# ProPrj_chuni_24_2026-08-18.net
KiCad netlist of a schematic drawn in EasyEDA Pro
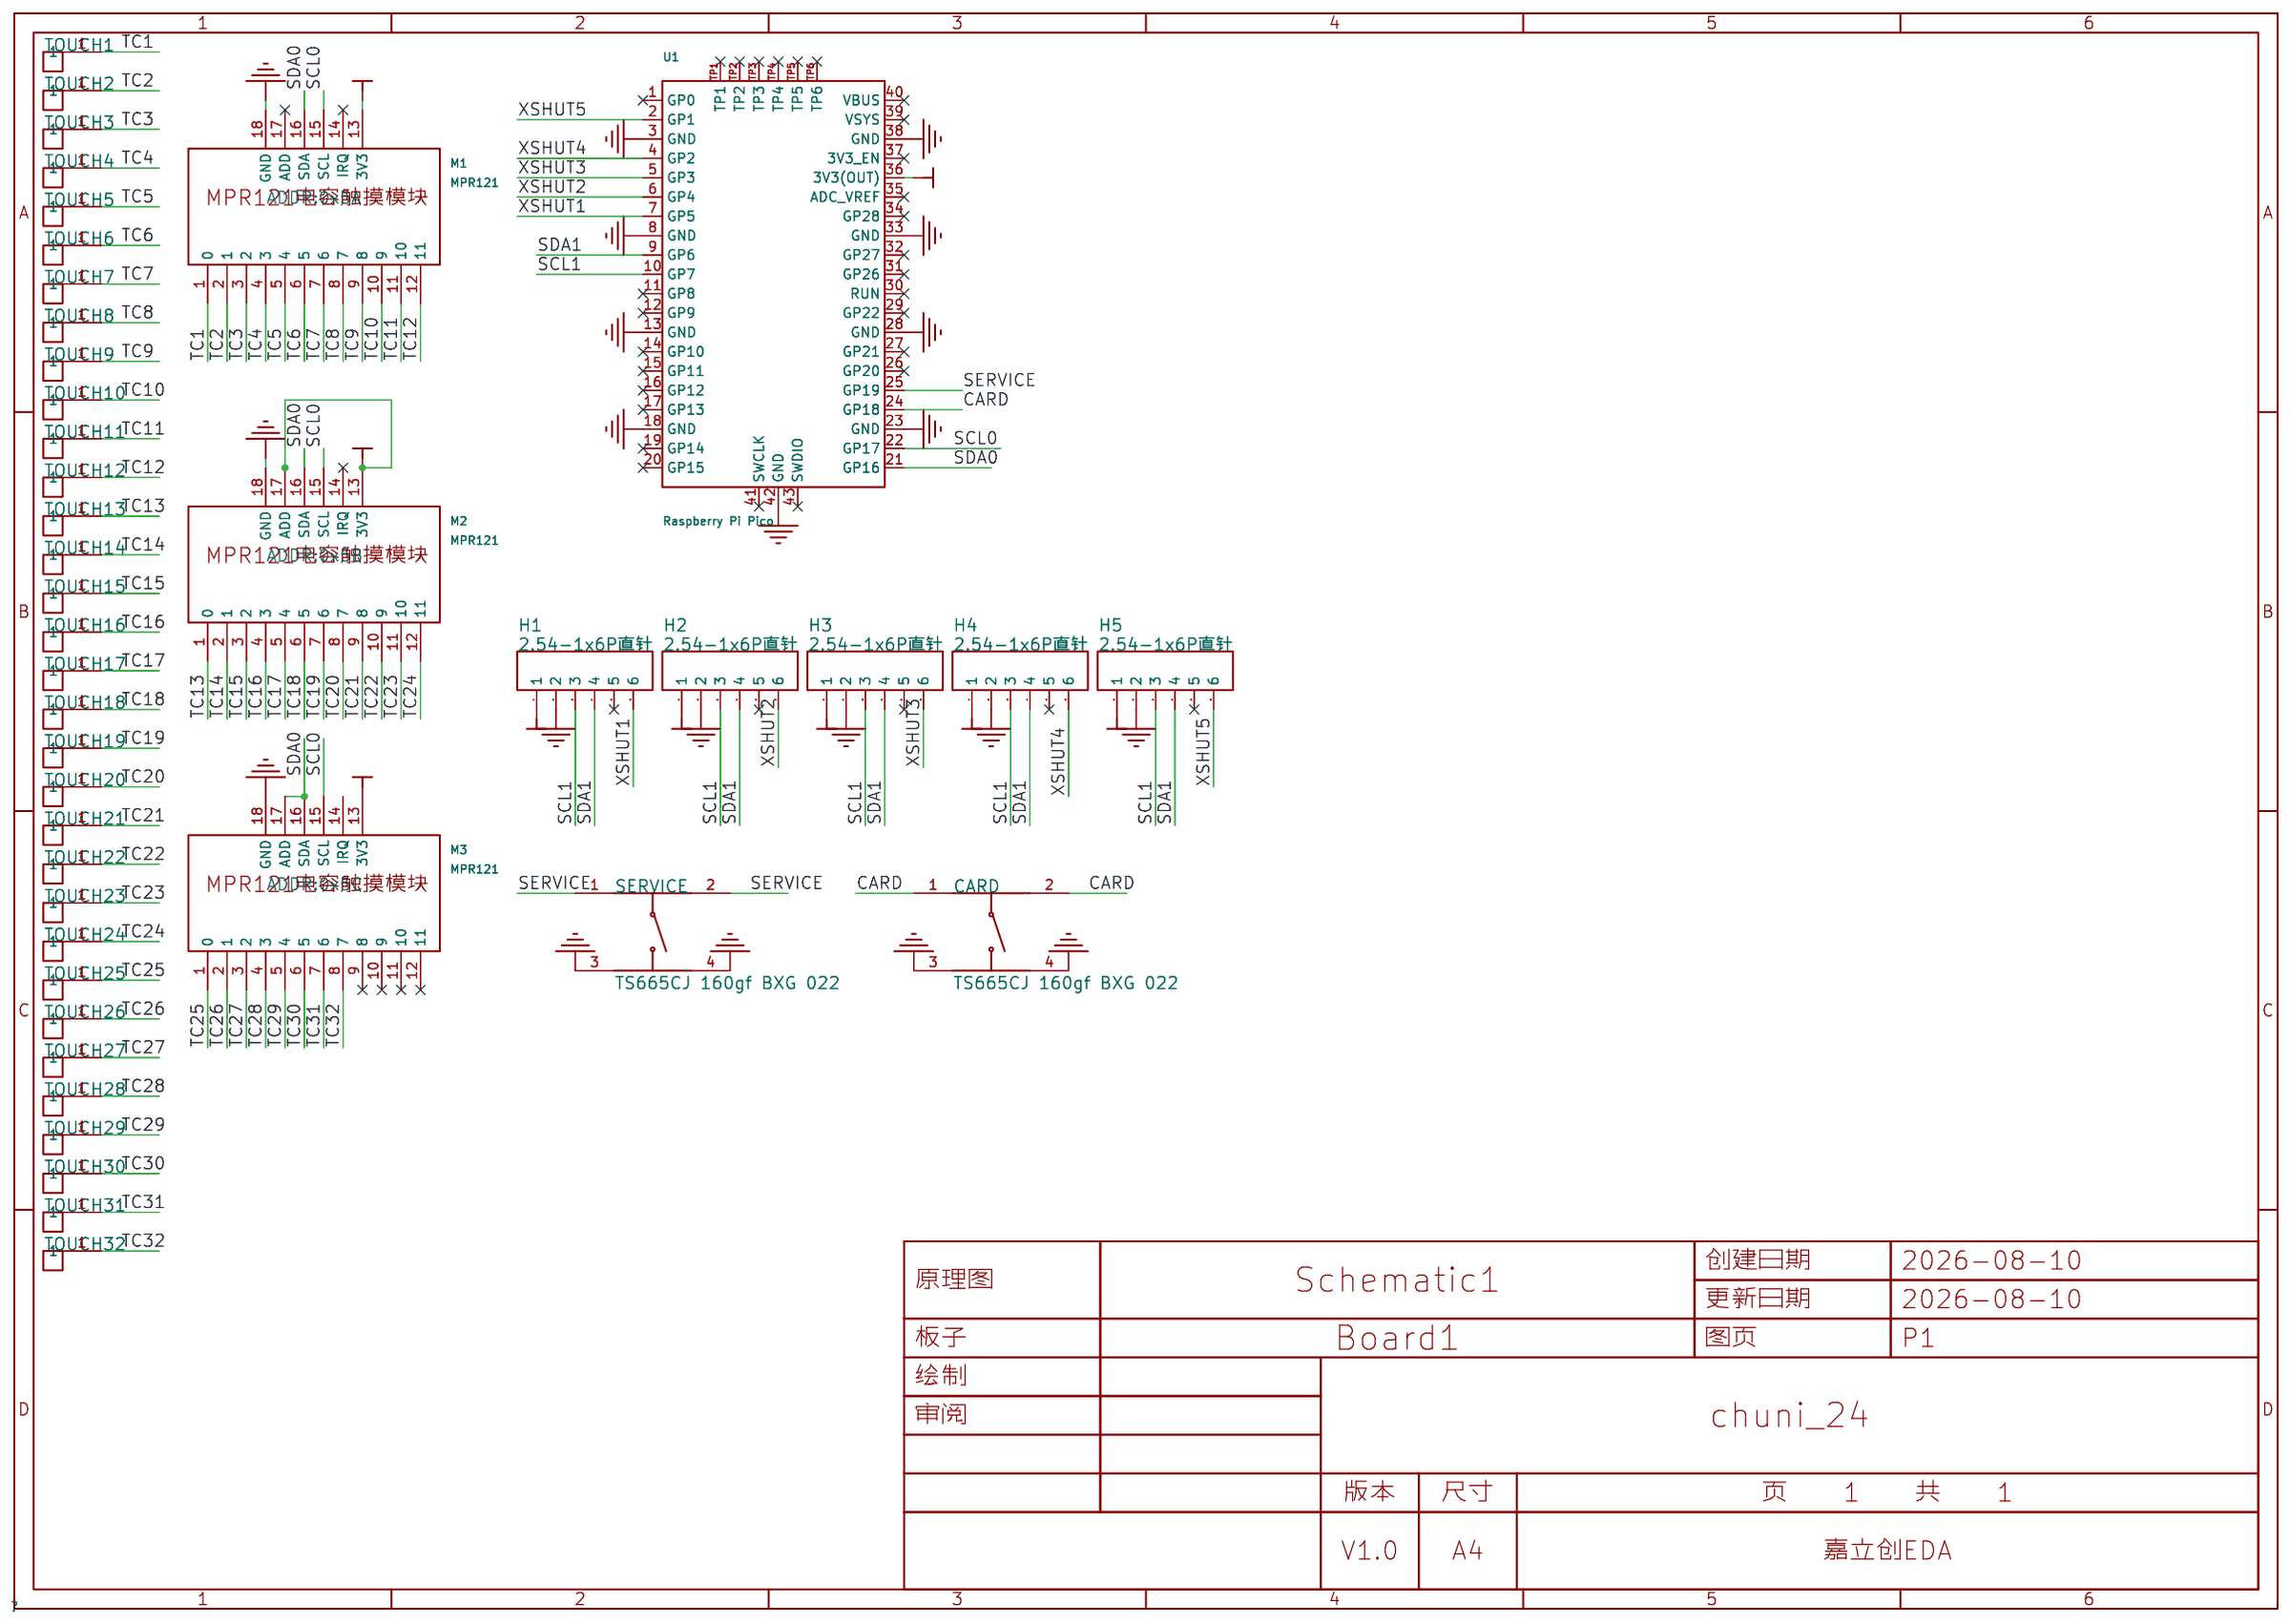
[diagram p0: schematic sheet]

(export (version "E")
  (design (tool "Eeschema 10.0.6"))
  (components
    (comp (ref "CARD")
      (value "TS665CJ 160gf BXG 022")
      (footprint "easyedapro:SW-TH_4P-L6.0-W6.0-P4.50-LS6.5")
      (fields (field (name "Manufacturer") "SHOU HAN(首韩)"))
      (libsource (lib "easyedapro") (part "TS665CJ 160GF BXG 022"))
    )
    (comp (ref "H1")
      (value "2.54-1x6P直针")
      (footprint "easyedapro:HDR-TH_6P-P2.54-V-M-1")
      (fields (field (name "Manufacturer") "BOOMELE(博穆精密)"))
      (libsource (lib "easyedapro") (part "Header-Male-2.54_1x6"))
    )
    (comp (ref "H2")
      (value "2.54-1x6P直针")
      (footprint "easyedapro:HDR-TH_6P-P2.54-V-M-1")
      (fields (field (name "Manufacturer") "BOOMELE(博穆精密)"))
      (libsource (lib "easyedapro") (part "Header-Male-2.54_1x6"))
    )
    (comp (ref "H3")
      (value "2.54-1x6P直针")
      (footprint "easyedapro:HDR-TH_6P-P2.54-V-M-1")
      (fields (field (name "Manufacturer") "BOOMELE(博穆精密)"))
      (libsource (lib "easyedapro") (part "Header-Male-2.54_1x6"))
    )
    (comp (ref "H4")
      (value "2.54-1x6P直针")
      (footprint "easyedapro:HDR-TH_6P-P2.54-V-M-1")
      (fields (field (name "Manufacturer") "BOOMELE(博穆精密)"))
      (libsource (lib "easyedapro") (part "Header-Male-2.54_1x6"))
    )
    (comp (ref "H5")
      (value "2.54-1x6P直针")
      (footprint "easyedapro:HDR-TH_6P-P2.54-V-M-1")
      (fields (field (name "Manufacturer") "BOOMELE(博穆精密)"))
      (libsource (lib "easyedapro") (part "Header-Male-2.54_1x6"))
    )
    (comp (ref "M1")
      (value "MPR121")
      (footprint "easyedapro:MPR121")
      (libsource (lib "easyedapro") (part "MPR121"))
    )
    (comp (ref "M2")
      (value "MPR121")
      (footprint "easyedapro:MPR121")
      (libsource (lib "easyedapro") (part "MPR121"))
    )
    (comp (ref "M3")
      (value "MPR121")
      (footprint "easyedapro:MPR121")
      (libsource (lib "easyedapro") (part "MPR121"))
    )
    (comp (ref "SERVICE")
      (value "TS665CJ 160gf BXG 022")
      (footprint "easyedapro:SW-TH_4P-L6.0-W6.0-P4.50-LS6.5")
      (fields (field (name "Manufacturer") "SHOU HAN(首韩)"))
      (libsource (lib "easyedapro") (part "TS665CJ 160GF BXG 022"))
    )
    (comp (ref "TOUCH1")
      (value "~")
      (footprint "easyedapro:touch_24.5")
      (libsource (lib "easyedapro") (part "touch_24.5"))
    )
    (comp (ref "TOUCH2")
      (value "~")
      (footprint "easyedapro:touch_24.5")
      (libsource (lib "easyedapro") (part "touch_24.5"))
    )
    (comp (ref "TOUCH3")
      (value "~")
      (footprint "easyedapro:touch_24.5")
      (libsource (lib "easyedapro") (part "touch_24.5"))
    )
    (comp (ref "TOUCH4")
      (value "~")
      (footprint "easyedapro:touch_24.5")
      (libsource (lib "easyedapro") (part "touch_24.5"))
    )
    (comp (ref "TOUCH5")
      (value "~")
      (footprint "easyedapro:touch_24.5")
      (libsource (lib "easyedapro") (part "touch_24.5"))
    )
    (comp (ref "TOUCH6")
      (value "~")
      (footprint "easyedapro:touch_24.5")
      (libsource (lib "easyedapro") (part "touch_24.5"))
    )
    (comp (ref "TOUCH7")
      (value "~")
      (footprint "easyedapro:touch_24.5")
      (libsource (lib "easyedapro") (part "touch_24.5"))
    )
    (comp (ref "TOUCH8")
      (value "~")
      (footprint "easyedapro:touch_24.5")
      (libsource (lib "easyedapro") (part "touch_24.5"))
    )
    (comp (ref "TOUCH9")
      (value "~")
      (footprint "easyedapro:touch_24.5")
      (libsource (lib "easyedapro") (part "touch_24.5"))
    )
    (comp (ref "TOUCH10")
      (value "~")
      (footprint "easyedapro:touch_24.5")
      (libsource (lib "easyedapro") (part "touch_24.5"))
    )
    (comp (ref "TOUCH11")
      (value "~")
      (footprint "easyedapro:touch_24.5")
      (libsource (lib "easyedapro") (part "touch_24.5"))
    )
    (comp (ref "TOUCH12")
      (value "~")
      (footprint "easyedapro:touch_24.5")
      (libsource (lib "easyedapro") (part "touch_24.5"))
    )
    (comp (ref "TOUCH13")
      (value "~")
      (footprint "easyedapro:touch_24.5")
      (libsource (lib "easyedapro") (part "touch_24.5"))
    )
    (comp (ref "TOUCH14")
      (value "~")
      (footprint "easyedapro:touch_24.5")
      (libsource (lib "easyedapro") (part "touch_24.5"))
    )
    (comp (ref "TOUCH15")
      (value "~")
      (footprint "easyedapro:touch_24.5")
      (libsource (lib "easyedapro") (part "touch_24.5"))
    )
    (comp (ref "TOUCH16")
      (value "~")
      (footprint "easyedapro:touch_24.5")
      (libsource (lib "easyedapro") (part "touch_24.5"))
    )
    (comp (ref "TOUCH17")
      (value "~")
      (footprint "easyedapro:touch_24.5")
      (libsource (lib "easyedapro") (part "touch_24.5"))
    )
    (comp (ref "TOUCH18")
      (value "~")
      (footprint "easyedapro:touch_24.5")
      (libsource (lib "easyedapro") (part "touch_24.5"))
    )
    (comp (ref "TOUCH19")
      (value "~")
      (footprint "easyedapro:touch_24.5")
      (libsource (lib "easyedapro") (part "touch_24.5"))
    )
    (comp (ref "TOUCH20")
      (value "~")
      (footprint "easyedapro:touch_24.5")
      (libsource (lib "easyedapro") (part "touch_24.5"))
    )
    (comp (ref "TOUCH21")
      (value "~")
      (footprint "easyedapro:touch_24.5")
      (libsource (lib "easyedapro") (part "touch_24.5"))
    )
    (comp (ref "TOUCH22")
      (value "~")
      (footprint "easyedapro:touch_24.5")
      (libsource (lib "easyedapro") (part "touch_24.5"))
    )
    (comp (ref "TOUCH23")
      (value "~")
      (footprint "easyedapro:touch_24.5")
      (libsource (lib "easyedapro") (part "touch_24.5"))
    )
    (comp (ref "TOUCH24")
      (value "~")
      (footprint "easyedapro:touch_24.5")
      (libsource (lib "easyedapro") (part "touch_24.5"))
    )
    (comp (ref "TOUCH25")
      (value "~")
      (footprint "easyedapro:touch_24.5")
      (libsource (lib "easyedapro") (part "touch_24.5"))
    )
    (comp (ref "TOUCH26")
      (value "~")
      (footprint "easyedapro:touch_24.5")
      (libsource (lib "easyedapro") (part "touch_24.5"))
    )
    (comp (ref "TOUCH27")
      (value "~")
      (footprint "easyedapro:touch_24.5")
      (libsource (lib "easyedapro") (part "touch_24.5"))
    )
    (comp (ref "TOUCH28")
      (value "~")
      (footprint "easyedapro:touch_24.5")
      (libsource (lib "easyedapro") (part "touch_24.5"))
    )
    (comp (ref "TOUCH29")
      (value "~")
      (footprint "easyedapro:touch_24.5")
      (libsource (lib "easyedapro") (part "touch_24.5"))
    )
    (comp (ref "TOUCH30")
      (value "~")
      (footprint "easyedapro:touch_24.5")
      (libsource (lib "easyedapro") (part "touch_24.5"))
    )
    (comp (ref "TOUCH31")
      (value "~")
      (footprint "easyedapro:touch_24.5")
      (libsource (lib "easyedapro") (part "touch_24.5"))
    )
    (comp (ref "TOUCH32")
      (value "~")
      (footprint "easyedapro:touch_24.5")
      (libsource (lib "easyedapro") (part "touch_24.5"))
    )
    (comp (ref "U1")
      (value "Raspberry Pi Pico")
      (footprint "easyedapro:COMM-SMD_L51.0-W21.0-P2.54_SC0916")
      (fields (field (name "Manufacturer") "Raspberry Pi(树莓派)"))
      (libsource (lib "easyedapro") (part "PICO"))
    )
  )
  (nets
    (net (code "1") (name "/CARD") (class "Default")
      (node (ref "CARD") (pin "1") (pinfunction "A_1") (pintype "unspecified"))
      (node (ref "CARD") (pin "2") (pinfunction "B_2") (pintype "unspecified"))
      (node (ref "U1") (pin "24") (pinfunction "GP18_24") (pintype "unspecified"))
    )
    (net (code "2") (name "/SCL0") (class "Default")
      (node (ref "M1") (pin "15") (pinfunction "SCL_15") (pintype "unspecified"))
      (node (ref "M2") (pin "15") (pinfunction "SCL_15") (pintype "unspecified"))
      (node (ref "M3") (pin "15") (pinfunction "SCL_15") (pintype "unspecified"))
      (node (ref "U1") (pin "22") (pinfunction "GP17_22") (pintype "unspecified"))
    )
    (net (code "3") (name "/SCL1") (class "Default")
      (node (ref "H1") (pin "3") (pinfunction "3_3") (pintype "input"))
      (node (ref "H2") (pin "3") (pinfunction "3_3") (pintype "input"))
      (node (ref "H3") (pin "3") (pinfunction "3_3") (pintype "input"))
      (node (ref "H4") (pin "3") (pinfunction "3_3") (pintype "input"))
      (node (ref "H5") (pin "3") (pinfunction "3_3") (pintype "input"))
      (node (ref "U1") (pin "10") (pinfunction "GP7_10") (pintype "unspecified"))
    )
    (net (code "4") (name "/SDA0") (class "Default")
      (node (ref "M1") (pin "16") (pinfunction "SDA_16") (pintype "unspecified"))
      (node (ref "M2") (pin "16") (pinfunction "SDA_16") (pintype "unspecified"))
      (node (ref "M3") (pin "16") (pinfunction "SDA_16") (pintype "unspecified"))
      (node (ref "M3") (pin "17") (pinfunction "ADD_17") (pintype "unspecified"))
      (node (ref "U1") (pin "21") (pinfunction "GP16_21") (pintype "unspecified"))
    )
    (net (code "5") (name "/SDA1") (class "Default")
      (node (ref "H1") (pin "4") (pinfunction "4_4") (pintype "input"))
      (node (ref "H2") (pin "4") (pinfunction "4_4") (pintype "input"))
      (node (ref "H3") (pin "4") (pinfunction "4_4") (pintype "input"))
      (node (ref "H4") (pin "4") (pinfunction "4_4") (pintype "input"))
      (node (ref "H5") (pin "4") (pinfunction "4_4") (pintype "input"))
      (node (ref "U1") (pin "9") (pinfunction "GP6_9") (pintype "unspecified"))
    )
    (net (code "6") (name "/SERVICE") (class "Default")
      (node (ref "SERVICE") (pin "1") (pinfunction "A_1") (pintype "unspecified"))
      (node (ref "SERVICE") (pin "2") (pinfunction "B_2") (pintype "unspecified"))
      (node (ref "U1") (pin "25") (pinfunction "GP19_25") (pintype "unspecified"))
    )
    (net (code "7") (name "/TC1") (class "Default")
      (node (ref "M1") (pin "1") (pinfunction "0_1") (pintype "unspecified"))
      (node (ref "TOUCH1") (pin "1") (pinfunction "1_1") (pintype "unspecified"))
    )
    (net (code "8") (name "/TC2") (class "Default")
      (node (ref "M1") (pin "2") (pinfunction "1_2") (pintype "unspecified"))
      (node (ref "TOUCH2") (pin "1") (pinfunction "1_1") (pintype "unspecified"))
    )
    (net (code "9") (name "/TC3") (class "Default")
      (node (ref "M1") (pin "3") (pinfunction "2_3") (pintype "unspecified"))
      (node (ref "TOUCH3") (pin "1") (pinfunction "1_1") (pintype "unspecified"))
    )
    (net (code "10") (name "/TC4") (class "Default")
      (node (ref "M1") (pin "4") (pinfunction "3_4") (pintype "unspecified"))
      (node (ref "TOUCH4") (pin "1") (pinfunction "1_1") (pintype "unspecified"))
    )
    (net (code "11") (name "/TC5") (class "Default")
      (node (ref "M1") (pin "5") (pinfunction "4_5") (pintype "unspecified"))
      (node (ref "TOUCH5") (pin "1") (pinfunction "1_1") (pintype "unspecified"))
    )
    (net (code "12") (name "/TC6") (class "Default")
      (node (ref "M1") (pin "6") (pinfunction "5_6") (pintype "unspecified"))
      (node (ref "TOUCH6") (pin "1") (pinfunction "1_1") (pintype "unspecified"))
    )
    (net (code "13") (name "/TC7") (class "Default")
      (node (ref "M1") (pin "7") (pinfunction "6_7") (pintype "unspecified"))
      (node (ref "TOUCH7") (pin "1") (pinfunction "1_1") (pintype "unspecified"))
    )
    (net (code "14") (name "/TC8") (class "Default")
      (node (ref "M1") (pin "8") (pinfunction "7_8") (pintype "unspecified"))
      (node (ref "TOUCH8") (pin "1") (pinfunction "1_1") (pintype "unspecified"))
    )
    (net (code "15") (name "/TC9") (class "Default")
      (node (ref "M1") (pin "9") (pinfunction "8_9") (pintype "unspecified"))
      (node (ref "TOUCH9") (pin "1") (pinfunction "1_1") (pintype "unspecified"))
    )
    (net (code "16") (name "/TC10") (class "Default")
      (node (ref "M1") (pin "10") (pinfunction "9_10") (pintype "unspecified"))
      (node (ref "TOUCH10") (pin "1") (pinfunction "1_1") (pintype "unspecified"))
    )
    (net (code "17") (name "/TC11") (class "Default")
      (node (ref "M1") (pin "11") (pinfunction "10_11") (pintype "unspecified"))
      (node (ref "TOUCH11") (pin "1") (pinfunction "1_1") (pintype "unspecified"))
    )
    (net (code "18") (name "/TC12") (class "Default")
      (node (ref "M1") (pin "12") (pinfunction "11_12") (pintype "unspecified"))
      (node (ref "TOUCH12") (pin "1") (pinfunction "1_1") (pintype "unspecified"))
    )
    (net (code "19") (name "/TC13") (class "Default")
      (node (ref "M2") (pin "1") (pinfunction "0_1") (pintype "unspecified"))
      (node (ref "TOUCH13") (pin "1") (pinfunction "1_1") (pintype "unspecified"))
    )
    (net (code "20") (name "/TC14") (class "Default")
      (node (ref "M2") (pin "2") (pinfunction "1_2") (pintype "unspecified"))
      (node (ref "TOUCH14") (pin "1") (pinfunction "1_1") (pintype "unspecified"))
    )
    (net (code "21") (name "/TC15") (class "Default")
      (node (ref "M2") (pin "3") (pinfunction "2_3") (pintype "unspecified"))
      (node (ref "TOUCH15") (pin "1") (pinfunction "1_1") (pintype "unspecified"))
    )
    (net (code "22") (name "/TC16") (class "Default")
      (node (ref "M2") (pin "4") (pinfunction "3_4") (pintype "unspecified"))
      (node (ref "TOUCH16") (pin "1") (pinfunction "1_1") (pintype "unspecified"))
    )
    (net (code "23") (name "/TC17") (class "Default")
      (node (ref "M2") (pin "5") (pinfunction "4_5") (pintype "unspecified"))
      (node (ref "TOUCH17") (pin "1") (pinfunction "1_1") (pintype "unspecified"))
    )
    (net (code "24") (name "/TC18") (class "Default")
      (node (ref "M2") (pin "6") (pinfunction "5_6") (pintype "unspecified"))
      (node (ref "TOUCH18") (pin "1") (pinfunction "1_1") (pintype "unspecified"))
    )
    (net (code "25") (name "/TC19") (class "Default")
      (node (ref "M2") (pin "7") (pinfunction "6_7") (pintype "unspecified"))
      (node (ref "TOUCH19") (pin "1") (pinfunction "1_1") (pintype "unspecified"))
    )
    (net (code "26") (name "/TC20") (class "Default")
      (node (ref "M2") (pin "8") (pinfunction "7_8") (pintype "unspecified"))
      (node (ref "TOUCH20") (pin "1") (pinfunction "1_1") (pintype "unspecified"))
    )
    (net (code "27") (name "/TC21") (class "Default")
      (node (ref "M2") (pin "9") (pinfunction "8_9") (pintype "unspecified"))
      (node (ref "TOUCH21") (pin "1") (pinfunction "1_1") (pintype "unspecified"))
    )
    (net (code "28") (name "/TC22") (class "Default")
      (node (ref "M2") (pin "10") (pinfunction "9_10") (pintype "unspecified"))
      (node (ref "TOUCH22") (pin "1") (pinfunction "1_1") (pintype "unspecified"))
    )
    (net (code "29") (name "/TC23") (class "Default")
      (node (ref "M2") (pin "11") (pinfunction "10_11") (pintype "unspecified"))
      (node (ref "TOUCH23") (pin "1") (pinfunction "1_1") (pintype "unspecified"))
    )
    (net (code "30") (name "/TC24") (class "Default")
      (node (ref "M2") (pin "12") (pinfunction "11_12") (pintype "unspecified"))
      (node (ref "TOUCH24") (pin "1") (pinfunction "1_1") (pintype "unspecified"))
    )
    (net (code "31") (name "/TC25") (class "Default")
      (node (ref "M3") (pin "1") (pinfunction "0_1") (pintype "unspecified"))
      (node (ref "TOUCH25") (pin "1") (pinfunction "1_1") (pintype "unspecified"))
    )
    (net (code "32") (name "/TC26") (class "Default")
      (node (ref "M3") (pin "2") (pinfunction "1_2") (pintype "unspecified"))
      (node (ref "TOUCH26") (pin "1") (pinfunction "1_1") (pintype "unspecified"))
    )
    (net (code "33") (name "/TC27") (class "Default")
      (node (ref "M3") (pin "3") (pinfunction "2_3") (pintype "unspecified"))
      (node (ref "TOUCH27") (pin "1") (pinfunction "1_1") (pintype "unspecified"))
    )
    (net (code "34") (name "/TC28") (class "Default")
      (node (ref "M3") (pin "4") (pinfunction "3_4") (pintype "unspecified"))
      (node (ref "TOUCH28") (pin "1") (pinfunction "1_1") (pintype "unspecified"))
    )
    (net (code "35") (name "/TC29") (class "Default")
      (node (ref "M3") (pin "5") (pinfunction "4_5") (pintype "unspecified"))
      (node (ref "TOUCH29") (pin "1") (pinfunction "1_1") (pintype "unspecified"))
    )
    (net (code "36") (name "/TC30") (class "Default")
      (node (ref "M3") (pin "6") (pinfunction "5_6") (pintype "unspecified"))
      (node (ref "TOUCH30") (pin "1") (pinfunction "1_1") (pintype "unspecified"))
    )
    (net (code "37") (name "/TC31") (class "Default")
      (node (ref "M3") (pin "7") (pinfunction "6_7") (pintype "unspecified"))
      (node (ref "TOUCH31") (pin "1") (pinfunction "1_1") (pintype "unspecified"))
    )
    (net (code "38") (name "/TC32") (class "Default")
      (node (ref "M3") (pin "8") (pinfunction "7_8") (pintype "unspecified"))
      (node (ref "TOUCH32") (pin "1") (pinfunction "1_1") (pintype "unspecified"))
    )
    (net (code "39") (name "/XSHUT1") (class "Default")
      (node (ref "H1") (pin "6") (pinfunction "6_6") (pintype "input"))
      (node (ref "U1") (pin "7") (pinfunction "GP5_7") (pintype "unspecified"))
    )
    (net (code "40") (name "/XSHUT2") (class "Default")
      (node (ref "H2") (pin "6") (pinfunction "6_6") (pintype "input"))
      (node (ref "U1") (pin "6") (pinfunction "GP4_6") (pintype "unspecified"))
    )
    (net (code "41") (name "/XSHUT3") (class "Default")
      (node (ref "H3") (pin "6") (pinfunction "6_6") (pintype "input"))
      (node (ref "U1") (pin "5") (pinfunction "GP3_5") (pintype "unspecified"))
    )
    (net (code "42") (name "/XSHUT4") (class "Default")
      (node (ref "H4") (pin "6") (pinfunction "6_6") (pintype "input"))
      (node (ref "U1") (pin "4") (pinfunction "GP2_4") (pintype "unspecified"))
    )
    (net (code "43") (name "/XSHUT5") (class "Default")
      (node (ref "H5") (pin "6") (pinfunction "6_6") (pintype "input"))
      (node (ref "U1") (pin "2") (pinfunction "GP1_2") (pintype "unspecified"))
    )
    (net (code "44") (name "GND") (class "Default")
      (node (ref "CARD") (pin "3") (pinfunction "C_3") (pintype "unspecified"))
      (node (ref "CARD") (pin "4") (pinfunction "D_4") (pintype "unspecified"))
      (node (ref "H1") (pin "2") (pinfunction "2_2") (pintype "input"))
      (node (ref "H2") (pin "2") (pinfunction "2_2") (pintype "input"))
      (node (ref "H3") (pin "2") (pinfunction "2_2") (pintype "input"))
      (node (ref "H4") (pin "2") (pinfunction "2_2") (pintype "input"))
      (node (ref "H5") (pin "2") (pinfunction "2_2") (pintype "input"))
      (node (ref "M1") (pin "18") (pinfunction "GND_18") (pintype "unspecified"))
      (node (ref "M2") (pin "18") (pinfunction "GND_18") (pintype "unspecified"))
      (node (ref "M3") (pin "18") (pinfunction "GND_18") (pintype "unspecified"))
      (node (ref "SERVICE") (pin "3") (pinfunction "C_3") (pintype "unspecified"))
      (node (ref "SERVICE") (pin "4") (pinfunction "D_4") (pintype "unspecified"))
      (node (ref "U1") (pin "13") (pinfunction "GND_13") (pintype "unspecified"))
      (node (ref "U1") (pin "18") (pinfunction "GND_18") (pintype "unspecified"))
      (node (ref "U1") (pin "23") (pinfunction "GND_23") (pintype "unspecified"))
      (node (ref "U1") (pin "28") (pinfunction "GND_28") (pintype "unspecified"))
      (node (ref "U1") (pin "3") (pinfunction "GND_3") (pintype "unspecified"))
      (node (ref "U1") (pin "33") (pinfunction "GND_33") (pintype "unspecified"))
      (node (ref "U1") (pin "38") (pinfunction "GND_38") (pintype "unspecified"))
      (node (ref "U1") (pin "42") (pinfunction "GND_42") (pintype "unspecified"))
      (node (ref "U1") (pin "8") (pinfunction "GND_8") (pintype "unspecified"))
    )
    (net (code "45") (name "VCC") (class "Default")
      (node (ref "H1") (pin "1") (pinfunction "1_1") (pintype "input"))
      (node (ref "H2") (pin "1") (pinfunction "1_1") (pintype "input"))
      (node (ref "H3") (pin "1") (pinfunction "1_1") (pintype "input"))
      (node (ref "H4") (pin "1") (pinfunction "1_1") (pintype "input"))
      (node (ref "H5") (pin "1") (pinfunction "1_1") (pintype "input"))
      (node (ref "M1") (pin "13") (pinfunction "3V3_13") (pintype "unspecified"))
      (node (ref "M2") (pin "13") (pinfunction "3V3_13") (pintype "unspecified"))
      (node (ref "M2") (pin "17") (pinfunction "ADD_17") (pintype "unspecified"))
      (node (ref "M3") (pin "13") (pinfunction "3V3_13") (pintype "unspecified"))
      (node (ref "U1") (pin "36") (pinfunction "3V3(OUT)_36") (pintype "unspecified"))
    )
    (net (code "46") (name "unconnected-(H1-Pad5)") (class "Default")
      (node (ref "H1") (pin "5") (pinfunction "5_5") (pintype "input+no_connect"))
    )
    (net (code "47") (name "unconnected-(H2-Pad5)") (class "Default")
      (node (ref "H2") (pin "5") (pinfunction "5_5") (pintype "input+no_connect"))
    )
    (net (code "48") (name "unconnected-(H3-Pad5)") (class "Default")
      (node (ref "H3") (pin "5") (pinfunction "5_5") (pintype "input+no_connect"))
    )
    (net (code "49") (name "unconnected-(H4-Pad5)") (class "Default")
      (node (ref "H4") (pin "5") (pinfunction "5_5") (pintype "input+no_connect"))
    )
    (net (code "50") (name "unconnected-(H5-Pad5)") (class "Default")
      (node (ref "H5") (pin "5") (pinfunction "5_5") (pintype "input+no_connect"))
    )
    (net (code "51") (name "unconnected-(M1-ADD-Pad17)") (class "Default")
      (node (ref "M1") (pin "17") (pinfunction "ADD_17") (pintype "unspecified+no_connect"))
    )
    (net (code "52") (name "unconnected-(M1-IRQ-Pad14)") (class "Default")
      (node (ref "M1") (pin "14") (pinfunction "IRQ_14") (pintype "unspecified+no_connect"))
    )
    (net (code "53") (name "unconnected-(M2-IRQ-Pad14)") (class "Default")
      (node (ref "M2") (pin "14") (pinfunction "IRQ_14") (pintype "unspecified+no_connect"))
    )
    (net (code "54") (name "unconnected-(M3-8-Pad9)") (class "Default")
      (node (ref "M3") (pin "9") (pinfunction "8_9") (pintype "unspecified+no_connect"))
    )
    (net (code "55") (name "unconnected-(M3-9-Pad10)") (class "Default")
      (node (ref "M3") (pin "10") (pinfunction "9_10") (pintype "unspecified+no_connect"))
    )
    (net (code "56") (name "unconnected-(M3-10-Pad11)") (class "Default")
      (node (ref "M3") (pin "11") (pinfunction "10_11") (pintype "unspecified+no_connect"))
    )
    (net (code "57") (name "unconnected-(M3-11-Pad12)") (class "Default")
      (node (ref "M3") (pin "12") (pinfunction "11_12") (pintype "unspecified+no_connect"))
    )
    (net (code "58") (name "unconnected-(M3-IRQ-Pad14)") (class "Default")
      (node (ref "M3") (pin "14") (pinfunction "IRQ_14") (pintype "unspecified"))
    )
    (net (code "59") (name "unconnected-(U1-3V3_EN-Pad37)") (class "Default")
      (node (ref "U1") (pin "37") (pinfunction "3V3_EN_37") (pintype "unspecified+no_connect"))
    )
    (net (code "60") (name "unconnected-(U1-ADC_VREF-Pad35)") (class "Default")
      (node (ref "U1") (pin "35") (pinfunction "ADC_VREF_35") (pintype "unspecified+no_connect"))
    )
    (net (code "61") (name "unconnected-(U1-GP0-Pad1)") (class "Default")
      (node (ref "U1") (pin "1") (pinfunction "GP0_1") (pintype "unspecified+no_connect"))
    )
    (net (code "62") (name "unconnected-(U1-GP8-Pad11)") (class "Default")
      (node (ref "U1") (pin "11") (pinfunction "GP8_11") (pintype "unspecified+no_connect"))
    )
    (net (code "63") (name "unconnected-(U1-GP9-Pad12)") (class "Default")
      (node (ref "U1") (pin "12") (pinfunction "GP9_12") (pintype "unspecified+no_connect"))
    )
    (net (code "64") (name "unconnected-(U1-GP10-Pad14)") (class "Default")
      (node (ref "U1") (pin "14") (pinfunction "GP10_14") (pintype "unspecified+no_connect"))
    )
    (net (code "65") (name "unconnected-(U1-GP11-Pad15)") (class "Default")
      (node (ref "U1") (pin "15") (pinfunction "GP11_15") (pintype "unspecified+no_connect"))
    )
    (net (code "66") (name "unconnected-(U1-GP12-Pad16)") (class "Default")
      (node (ref "U1") (pin "16") (pinfunction "GP12_16") (pintype "unspecified+no_connect"))
    )
    (net (code "67") (name "unconnected-(U1-GP13-Pad17)") (class "Default")
      (node (ref "U1") (pin "17") (pinfunction "GP13_17") (pintype "unspecified+no_connect"))
    )
    (net (code "68") (name "unconnected-(U1-GP14-Pad19)") (class "Default")
      (node (ref "U1") (pin "19") (pinfunction "GP14_19") (pintype "unspecified+no_connect"))
    )
    (net (code "69") (name "unconnected-(U1-GP15-Pad20)") (class "Default")
      (node (ref "U1") (pin "20") (pinfunction "GP15_20") (pintype "unspecified+no_connect"))
    )
    (net (code "70") (name "unconnected-(U1-GP20-Pad26)") (class "Default")
      (node (ref "U1") (pin "26") (pinfunction "GP20_26") (pintype "unspecified+no_connect"))
    )
    (net (code "71") (name "unconnected-(U1-GP21-Pad27)") (class "Default")
      (node (ref "U1") (pin "27") (pinfunction "GP21_27") (pintype "unspecified+no_connect"))
    )
    (net (code "72") (name "unconnected-(U1-GP22-Pad29)") (class "Default")
      (node (ref "U1") (pin "29") (pinfunction "GP22_29") (pintype "unspecified+no_connect"))
    )
    (net (code "73") (name "unconnected-(U1-GP26-Pad31)") (class "Default")
      (node (ref "U1") (pin "31") (pinfunction "GP26_31") (pintype "unspecified+no_connect"))
    )
    (net (code "74") (name "unconnected-(U1-GP27-Pad32)") (class "Default")
      (node (ref "U1") (pin "32") (pinfunction "GP27_32") (pintype "unspecified+no_connect"))
    )
    (net (code "75") (name "unconnected-(U1-GP28-Pad34)") (class "Default")
      (node (ref "U1") (pin "34") (pinfunction "GP28_34") (pintype "unspecified+no_connect"))
    )
    (net (code "76") (name "unconnected-(U1-PadTP1)") (class "Default")
      (node (ref "U1") (pin "TP1") (pinfunction "TP1_TP1") (pintype "unspecified+no_connect"))
    )
    (net (code "77") (name "unconnected-(U1-PadTP2)") (class "Default")
      (node (ref "U1") (pin "TP2") (pinfunction "TP2_TP2") (pintype "unspecified+no_connect"))
    )
    (net (code "78") (name "unconnected-(U1-PadTP3)") (class "Default")
      (node (ref "U1") (pin "TP3") (pinfunction "TP3_TP3") (pintype "unspecified+no_connect"))
    )
    (net (code "79") (name "unconnected-(U1-PadTP4)") (class "Default")
      (node (ref "U1") (pin "TP4") (pinfunction "TP4_TP4") (pintype "unspecified+no_connect"))
    )
    (net (code "80") (name "unconnected-(U1-PadTP5)") (class "Default")
      (node (ref "U1") (pin "TP5") (pinfunction "TP5_TP5") (pintype "unspecified+no_connect"))
    )
    (net (code "81") (name "unconnected-(U1-PadTP6)") (class "Default")
      (node (ref "U1") (pin "TP6") (pinfunction "TP6_TP6") (pintype "unspecified+no_connect"))
    )
    (net (code "82") (name "unconnected-(U1-RUN-Pad30)") (class "Default")
      (node (ref "U1") (pin "30") (pinfunction "RUN_30") (pintype "unspecified+no_connect"))
    )
    (net (code "83") (name "unconnected-(U1-SWCLK-Pad41)") (class "Default")
      (node (ref "U1") (pin "41") (pinfunction "SWCLK_41") (pintype "unspecified+no_connect"))
    )
    (net (code "84") (name "unconnected-(U1-SWDIO-Pad43)") (class "Default")
      (node (ref "U1") (pin "43") (pinfunction "SWDIO_43") (pintype "unspecified+no_connect"))
    )
    (net (code "85") (name "unconnected-(U1-VBUS-Pad40)") (class "Default")
      (node (ref "U1") (pin "40") (pinfunction "VBUS_40") (pintype "unspecified+no_connect"))
    )
    (net (code "86") (name "unconnected-(U1-VSYS-Pad39)") (class "Default")
      (node (ref "U1") (pin "39") (pinfunction "VSYS_39") (pintype "unspecified+no_connect"))
    )
  )
)
